# CW340_USBHUB.net
KiCad netlist of a schematic drawn in Altium Designer
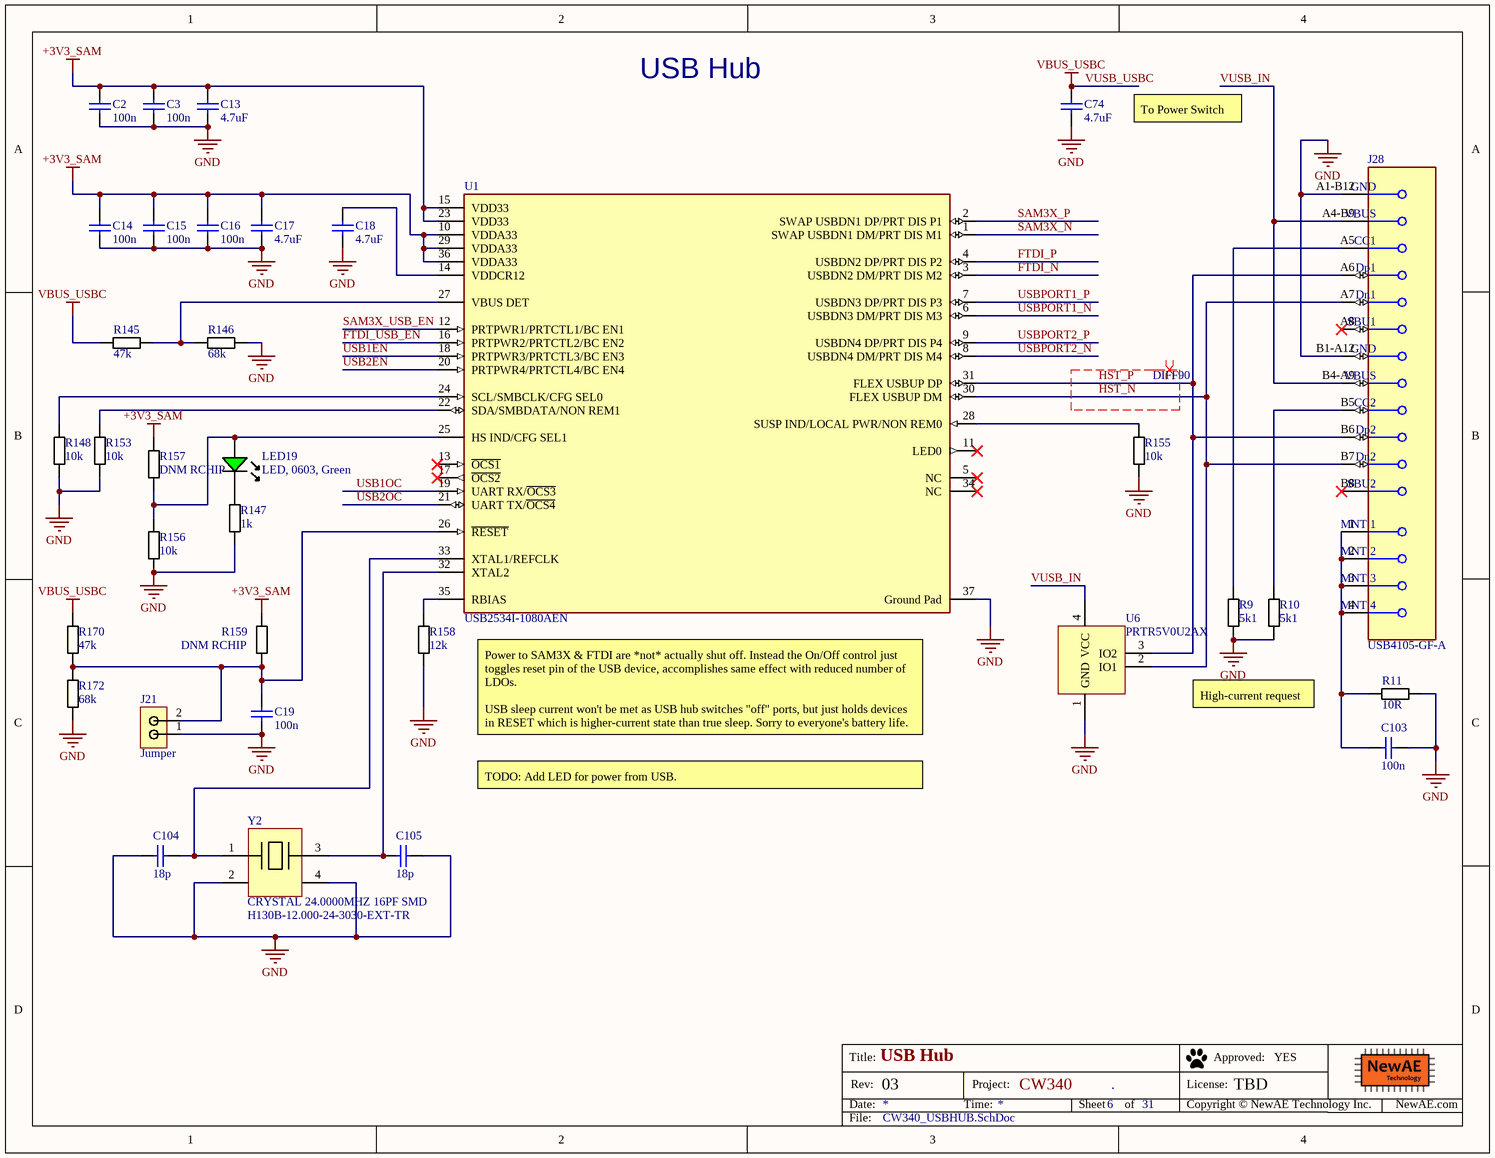
[diagram p0: CW340_USBHUB.SchDoc]

(export (version "E")
  (design (tool "Eeschema 10.0.6"))
  (components
    (comp (ref "C2")
      (value "100n")
      (footprint "CAPC0402_M")
      (description "100n, 0402")
      (fields (field (name "PART NUMBER") "CCHIP-100n-0402"))
      (libsource (lib "NewAE_AltiumLib") (part "CAP"))
    )
    (comp (ref "C3")
      (value "100n")
      (footprint "CAPC0402_M")
      (description "100n, 0402")
      (fields (field (name "PART NUMBER") "CCHIP-100n-0402"))
      (libsource (lib "NewAE_AltiumLib") (part "CAP"))
    )
    (comp (ref "C13")
      (value "4.7uF")
      (footprint "CAPC0805_M")
      (description "4u7, 35V, 0805, Ceramic")
      (fields (field (name "PART NUMBER") "CCHIP-4u7-0805-35V") (field (name "TOLERANCE") "10%"))
      (libsource (lib "NewAE_AltiumLib") (part "CAP"))
    )
    (comp (ref "C14")
      (value "100n")
      (footprint "CAPC0402_M")
      (description "100n, 0402")
      (fields (field (name "PART NUMBER") "CCHIP-100n-0402"))
      (libsource (lib "NewAE_AltiumLib") (part "CAP"))
    )
    (comp (ref "C15")
      (value "100n")
      (footprint "CAPC0402_M")
      (description "100n, 0402")
      (fields (field (name "PART NUMBER") "CCHIP-100n-0402"))
      (libsource (lib "NewAE_AltiumLib") (part "CAP"))
    )
    (comp (ref "C16")
      (value "100n")
      (footprint "CAPC0402_M")
      (description "100n, 0402")
      (fields (field (name "PART NUMBER") "CCHIP-100n-0402"))
      (libsource (lib "NewAE_AltiumLib") (part "CAP"))
    )
    (comp (ref "C17")
      (value "4.7uF")
      (footprint "CAPC0805_M")
      (description "4u7, 35V, 0805, Ceramic")
      (fields (field (name "PART NUMBER") "CCHIP-4u7-0805-35V") (field (name "TOLERANCE") "10%"))
      (libsource (lib "NewAE_AltiumLib") (part "CAP"))
    )
    (comp (ref "C18")
      (value "4.7uF")
      (footprint "CAPC0805_M")
      (description "4u7, 35V, 0805, Ceramic")
      (fields (field (name "PART NUMBER") "CCHIP-4u7-0805-35V") (field (name "TOLERANCE") "10%"))
      (libsource (lib "NewAE_AltiumLib") (part "CAP"))
    )
    (comp (ref "C19")
      (value "100n")
      (footprint "CAPC0402_M")
      (description "100n, 0402")
      (fields (field (name "PART NUMBER") "CCHIP-100n-0402"))
      (libsource (lib "NewAE_AltiumLib") (part "CAP"))
    )
    (comp (ref "C74")
      (value "4.7uF")
      (footprint "CAPC0805_M")
      (description "4u7, 35V, 0805, Ceramic")
      (fields (field (name "PART NUMBER") "CCHIP-4u7-0805-35V") (field (name "TOLERANCE") "10%"))
      (libsource (lib "NewAE_AltiumLib") (part "CAP"))
    )
    (comp (ref "C103")
      (value "100n")
      (footprint "CAPC0603_M")
      (description "100n, 0603")
      (fields (field (name "PART NUMBER") "CCHIP-100n-0603"))
      (libsource (lib "NewAE_AltiumLib") (part "CAP"))
    )
    (comp (ref "C104")
      (value "18p")
      (footprint "CAPC0402_M")
      (description "18p, 0402")
      (fields (field (name "PART NUMBER") "CCHIP-18p-0402"))
      (libsource (lib "NewAE_AltiumLib") (part "CAP"))
    )
    (comp (ref "C105")
      (value "18p")
      (footprint "CAPC0402_M")
      (description "18p, 0402")
      (fields (field (name "PART NUMBER") "CCHIP-18p-0402"))
      (libsource (lib "NewAE_AltiumLib") (part "CAP"))
    )
    (comp (ref "J21")
      (value "Jumper")
      (footprint "2x2.54mm_Header")
      (description "1x2 2.54mm header, male pins")
      (fields (field (name "PART NUMBER") "2_PIN_JUMPER"))
      (libsource (lib "NewAE_AltiumLib") (part "1x2_Pin_Header"))
    )
    (comp (ref "J28")
      (value "USB4105-GF-A")
      (footprint "FP-USB4105-GF-A-MFG")
      (description "CONN RCPT USB2.0 TYPEC 5A")
      (fields
        (field (name "MANUFACTURER") "GCT")
        (field (name "OCTOPART") "https://octopart.com/usb4105-gf-a-gct-106627878")
      )
      (libsource (lib "Altium Content Vault") (part "e7c17a616881a82b79941196b4bec10"))
    )
    (comp (ref "LED19")
      (value "LED, 0603, Green")
      (footprint "LED-0603-GREEN")
      (description "Chip LED, Green")
      (fields (field (name "PART NUMBER") "LEDCHIP_0603_GREEN"))
      (libsource (lib "NewAE_AltiumLib") (part "LED_GREEN"))
    )
    (comp (ref "R9")
      (value "5k1")
      (footprint "RESC1608X55N")
      (description "5k1 res, 0603, 1%, 1/10W")
      (fields (field (name "PART NUMBER") "RCHIP-5K1-0603") (field (name "TOLERANCE") "1%"))
      (libsource (lib "") (part "RES-EU_2"))
    )
    (comp (ref "R10")
      (value "5k1")
      (footprint "RESC1608X55N")
      (description "5k1 res, 0603, 1%, 1/10W")
      (fields (field (name "PART NUMBER") "RCHIP-5K1-0603") (field (name "TOLERANCE") "1%"))
      (libsource (lib "") (part "RES-EU_2"))
    )
    (comp (ref "R11")
      (value "10R")
      (footprint "RESC1608X55N")
      (description "10R res, 0603, 1%, 1/10W")
      (fields (field (name "PART NUMBER") "RCHIP-10R-0603") (field (name "TOLERANCE") "1%"))
      (libsource (lib "") (part "RES-EU_1"))
    )
    (comp (ref "R145")
      (value "47k")
      (footprint "RESC1608X55N")
      (description "47k res, 0603, 1%, 1/10W")
      (fields (field (name "PART NUMBER") "RCHIP-47K-0603") (field (name "TOLERANCE") "1%"))
      (libsource (lib "") (part "RES-EU_1"))
    )
    (comp (ref "R146")
      (value "68k")
      (footprint "RESC1608X55N")
      (description "68k res, 0603, 1%, 1/10W")
      (fields (field (name "PART NUMBER") "RCHIP-68K-0603") (field (name "TOLERANCE") "1%"))
      (libsource (lib "") (part "RES-EU_1"))
    )
    (comp (ref "R147")
      (value "1k")
      (footprint "RESC1608X55N")
      (description "1k res, 0603, 1%, 1/10W")
      (fields (field (name "PART NUMBER") "RCHIP-1K-0603") (field (name "TOLERANCE") "1%"))
      (libsource (lib "") (part "RES-EU_2"))
    )
    (comp (ref "R148")
      (value "10k")
      (footprint "RESC1608X55N")
      (description "10k res, 0603, 1%, 1/10W")
      (fields (field (name "PART NUMBER") "RCHIP-10K-0603") (field (name "TOLERANCE") "1%"))
      (libsource (lib "NewAE_AltiumLib") (part "RES-EU"))
    )
    (comp (ref "R153")
      (value "10k")
      (footprint "RESC1608X55N")
      (description "10k res, 0603, 1%, 1/10W")
      (fields (field (name "PART NUMBER") "RCHIP-10K-0603") (field (name "TOLERANCE") "1%"))
      (libsource (lib "NewAE_AltiumLib") (part "RES-EU"))
    )
    (comp (ref "R155")
      (value "10k")
      (footprint "RESC1608X55N")
      (description "10k res, 0603, 1%, 1/10W")
      (fields (field (name "PART NUMBER") "RCHIP-10K-0603") (field (name "TOLERANCE") "1%"))
      (libsource (lib "NewAE_AltiumLib") (part "RES-EU"))
    )
    (comp (ref "R156")
      (value "10k")
      (footprint "RESC1608X55N")
      (description "10k res, 0603, 1%, 1/10W")
      (fields (field (name "PART NUMBER") "RCHIP-10K-0603") (field (name "TOLERANCE") "1%"))
      (libsource (lib "") (part "RES-EU_2"))
    )
    (comp (ref "R157")
      (value "DNM RCHIP")
      (footprint "RESC1608X55N")
      (description "Do Not Mount Resistor")
      (fields (field (name "PART NUMBER") "RCHIP-DNM-0603"))
      (libsource (lib "") (part "RES-EU_2"))
    )
    (comp (ref "R158")
      (value "12k")
      (footprint "RESC1608X55N")
      (description "12k res, 0603, 1%, 1/10W")
      (fields (field (name "PART NUMBER") "RCHIP-12K-0603") (field (name "TOLERANCE") "1%"))
      (libsource (lib "") (part "RES-EU_2"))
    )
    (comp (ref "R159")
      (value "DNM RCHIP")
      (footprint "RESC1608X55N")
      (description "Do Not Mount Resistor")
      (fields (field (name "PART NUMBER") "RCHIP-DNM-0603"))
      (libsource (lib "") (part "RES-EU_2"))
    )
    (comp (ref "R170")
      (value "47k")
      (footprint "RESC1608X55N")
      (description "47k res, 0603, 1%, 1/10W")
      (fields (field (name "PART NUMBER") "RCHIP-47K-0603") (field (name "TOLERANCE") "1%"))
      (libsource (lib "") (part "RES-EU_2"))
    )
    (comp (ref "R172")
      (value "68k")
      (footprint "RESC1608X55N")
      (description "68k res, 0603, 1%, 1/10W")
      (fields (field (name "PART NUMBER") "RCHIP-68K-0603") (field (name "TOLERANCE") "1%"))
      (libsource (lib "NewAE_AltiumLib") (part "RES-EU"))
    )
    (comp (ref "U1")
      (value "USB2534I-1080AEN")
      (footprint "FP-36SQFN-3706-6x6B-IPC_C")
      (description "IC USB 2.0 HUB CTLR 4PORT 36SQFN")
      (libsource (lib "Altium Content Vault") (part "de4cb607940eb19a3e56e20a470d684"))
    )
    (comp (ref "U6")
      (value "PRTR5V0U2AX")
      (footprint "SOT143B")
      (description "USB 2.0 high-speed ESD")
      (libsource (lib "CW550_MAIN") (part "PRTR5V0U2AX"))
    )
    (comp (ref "Y2")
      (value "CRYSTAL 24.0000MHZ 16PF SMD")
      (footprint "5x3.2MM XTAL")
      (description "24MHz ±30ppm Crystal 16pF 35 Ohms 4-SMD, No Lead")
      (fields
        (field (name "MANUFACTURER") "Raltron Electronics")
        (field (name "MANUFACTURER PART NUMBER") "H130B-12.000-24-3030-EXT-TR")
        (field (name "PART NUMBER") "H130B-24.000-18-3030-EXT-TR")
      )
      (libsource (lib "NewAE_AltiumLib") (part "H130B-12.000-16-2525-EXT-TR"))
    )
  )
  (nets
    (net (code "1") (name "+3V3_SAM") (class "Default")
      (node (ref "C13") (pin "1") (pinfunction "1_1") (pintype "passive"))
      (node (ref "C14") (pin "1") (pinfunction "1_1") (pintype "passive"))
      (node (ref "C15") (pin "1") (pinfunction "1_1") (pintype "passive"))
      (node (ref "C16") (pin "1") (pinfunction "1_1") (pintype "passive"))
      (node (ref "C17") (pin "1") (pinfunction "1_1") (pintype "passive"))
      (node (ref "C2") (pin "1") (pinfunction "1_1") (pintype "passive"))
      (node (ref "C3") (pin "1") (pinfunction "1_1") (pintype "passive"))
      (node (ref "R157") (pin "1") (pinfunction "1_1") (pintype "passive"))
      (node (ref "R159") (pin "1") (pinfunction "1_1") (pintype "passive"))
      (node (ref "U1") (pin "10") (pinfunction "VDDA33_10") (pintype "power_in"))
      (node (ref "U1") (pin "15") (pinfunction "VDD33_15") (pintype "power_in"))
      (node (ref "U1") (pin "23") (pinfunction "VDD33_23") (pintype "power_in"))
      (node (ref "U1") (pin "29") (pinfunction "VDDA33_29") (pintype "power_in"))
      (node (ref "U1") (pin "36") (pinfunction "VDDA33_36") (pintype "power_in"))
    )
    (net (code "2") (name "/FTDI_N") (class "Default")
      (node (ref "U1") (pin "3") (pinfunction "USBDN2_DM/PRT_DIS_M2_3") (pintype "bidirectional"))
    )
    (net (code "3") (name "/FTDI_P") (class "Default")
      (node (ref "U1") (pin "4") (pinfunction "USBDN2_DP/PRT_DIS_P2_4") (pintype "bidirectional"))
    )
    (net (code "4") (name "/FTDI_USB_EN") (class "Default")
      (node (ref "U1") (pin "16") (pinfunction "PRTPWR2/PRTCTL2/BC_EN2_16") (pintype "input"))
    )
    (net (code "5") (name "/HST_N") (class "Default")
      (node (ref "J28") (pin "A7") (pinfunction "Dn1_A7") (pintype "bidirectional"))
      (node (ref "J28") (pin "B7") (pinfunction "Dn2_B7") (pintype "bidirectional"))
      (node (ref "U1") (pin "30") (pinfunction "FLEX_USBUP_DM_30") (pintype "bidirectional"))
      (node (ref "U6") (pin "2") (pinfunction "IO1_2") (pintype "passive"))
    )
    (net (code "6") (name "/HST_P") (class "Default")
      (node (ref "J28") (pin "A6") (pinfunction "Dp1_A6") (pintype "bidirectional"))
      (node (ref "J28") (pin "B6") (pinfunction "Dp2_B6") (pintype "bidirectional"))
      (node (ref "U1") (pin "31") (pinfunction "FLEX_USBUP_DP_31") (pintype "bidirectional"))
      (node (ref "U6") (pin "3") (pinfunction "IO2_3") (pintype "passive"))
    )
    (net (code "7") (name "/SAM3X_N") (class "Default")
      (node (ref "U1") (pin "1") (pinfunction "SWAP_USBDN1_DM/PRT_DIS_M1_1") (pintype "bidirectional"))
    )
    (net (code "8") (name "/SAM3X_P") (class "Default")
      (node (ref "U1") (pin "2") (pinfunction "SWAP_USBDN1_DP/PRT_DIS_P1_2") (pintype "bidirectional"))
    )
    (net (code "9") (name "/SAM3X_USB_EN") (class "Default")
      (node (ref "U1") (pin "12") (pinfunction "PRTPWR1/PRTCTL1/BC_EN1_12") (pintype "input"))
    )
    (net (code "10") (name "/USB1EN") (class "Default")
      (node (ref "U1") (pin "18") (pinfunction "PRTPWR3/PRTCTL3/BC_EN3_18") (pintype "input"))
    )
    (net (code "11") (name "/USB1OC") (class "Default")
      (node (ref "U1") (pin "19") (pinfunction "UART_RX/~{OCS3}_19") (pintype "input"))
    )
    (net (code "12") (name "/USB2EN") (class "Default")
      (node (ref "U1") (pin "20") (pinfunction "PRTPWR4/PRTCTL4/BC_EN4_20") (pintype "input"))
    )
    (net (code "13") (name "/USB2OC") (class "Default")
      (node (ref "U1") (pin "21") (pinfunction "UART_TX/~{OCS4}_21") (pintype "bidirectional"))
    )
    (net (code "14") (name "/USBPORT1_N") (class "Default")
      (node (ref "U1") (pin "6") (pinfunction "USBDN3_DM/PRT_DIS_M3_6") (pintype "bidirectional"))
    )
    (net (code "15") (name "/USBPORT1_P") (class "Default")
      (node (ref "U1") (pin "7") (pinfunction "USBDN3_DP/PRT_DIS_P3_7") (pintype "bidirectional"))
    )
    (net (code "16") (name "/USBPORT2_N") (class "Default")
      (node (ref "U1") (pin "8") (pinfunction "USBDN4_DM/PRT_DIS_M4_8") (pintype "bidirectional"))
    )
    (net (code "17") (name "/USBPORT2_P") (class "Default")
      (node (ref "U1") (pin "9") (pinfunction "USBDN4_DP/PRT_DIS_P4_9") (pintype "bidirectional"))
    )
    (net (code "18") (name "/VUSB_IN") (class "Default")
      (node (ref "J28") (pin "A4-B9") (pinfunction "VBUS_A4-B9") (pintype "power_in"))
      (node (ref "J28") (pin "B4-A9") (pinfunction "VBUS_B4-A9") (pintype "bidirectional"))
      (node (ref "U6") (pin "4") (pinfunction "VCC_4") (pintype "power_in"))
    )
    (net (code "19") (name "GND") (class "Default")
      (node (ref "C103") (pin "2") (pinfunction "2_2") (pintype "passive"))
      (node (ref "C104") (pin "1") (pinfunction "1_1") (pintype "passive"))
      (node (ref "C105") (pin "2") (pinfunction "2_2") (pintype "passive"))
      (node (ref "C13") (pin "2") (pinfunction "2_2") (pintype "passive"))
      (node (ref "C14") (pin "2") (pinfunction "2_2") (pintype "passive"))
      (node (ref "C15") (pin "2") (pinfunction "2_2") (pintype "passive"))
      (node (ref "C16") (pin "2") (pinfunction "2_2") (pintype "passive"))
      (node (ref "C17") (pin "2") (pinfunction "2_2") (pintype "passive"))
      (node (ref "C18") (pin "1") (pinfunction "1_1") (pintype "passive"))
      (node (ref "C19") (pin "2") (pinfunction "2_2") (pintype "passive"))
      (node (ref "C2") (pin "2") (pinfunction "2_2") (pintype "passive"))
      (node (ref "C3") (pin "2") (pinfunction "2_2") (pintype "passive"))
      (node (ref "C74") (pin "2") (pinfunction "2_2") (pintype "passive"))
      (node (ref "J21") (pin "1") (pinfunction "1_1") (pintype "passive"))
      (node (ref "J28") (pin "A1-B12") (pinfunction "GND_A1-B12") (pintype "power_in"))
      (node (ref "J28") (pin "B1-A12") (pinfunction "GND_B1-A12") (pintype "bidirectional"))
      (node (ref "R10") (pin "2") (pinfunction "2_2") (pintype "passive"))
      (node (ref "R11") (pin "2") (pinfunction "2_2") (pintype "passive"))
      (node (ref "R146") (pin "2") (pinfunction "2_2") (pintype "passive"))
      (node (ref "R147") (pin "2") (pinfunction "2_2") (pintype "passive"))
      (node (ref "R148") (pin "1") (pinfunction "1_1") (pintype "passive"))
      (node (ref "R153") (pin "1") (pinfunction "1_1") (pintype "passive"))
      (node (ref "R155") (pin "1") (pinfunction "1_1") (pintype "passive"))
      (node (ref "R156") (pin "2") (pinfunction "2_2") (pintype "passive"))
      (node (ref "R158") (pin "2") (pinfunction "2_2") (pintype "passive"))
      (node (ref "R172") (pin "1") (pinfunction "1_1") (pintype "passive"))
      (node (ref "R9") (pin "2") (pinfunction "2_2") (pintype "passive"))
      (node (ref "U1") (pin "37") (pinfunction "Ground_Pad_37") (pintype "power_in"))
      (node (ref "U6") (pin "1") (pinfunction "GND_1") (pintype "power_in"))
      (node (ref "Y2") (pin "2") (pinfunction "2_2") (pintype "passive"))
      (node (ref "Y2") (pin "4") (pinfunction "4_4") (pintype "passive"))
    )
    (net (code "20") (name "Net-(J28-CC1)") (class "Default")
      (node (ref "J28") (pin "A5") (pinfunction "CC1_A5") (pintype "power_in"))
      (node (ref "R9") (pin "1") (pinfunction "1_1") (pintype "passive"))
    )
    (net (code "21") (name "Net-(J28-CC2)") (class "Default")
      (node (ref "J28") (pin "B5") (pinfunction "CC2_B5") (pintype "bidirectional"))
      (node (ref "R10") (pin "1") (pinfunction "1_1") (pintype "passive"))
    )
    (net (code "22") (name "Net-(J28-MNT_1)") (class "Default")
      (node (ref "C103") (pin "1") (pinfunction "1_1") (pintype "passive"))
      (node (ref "J28") (pin "1") (pinfunction "MNT_1_1") (pintype "power_in"))
      (node (ref "J28") (pin "2") (pinfunction "MNT_2_2") (pintype "power_in"))
      (node (ref "J28") (pin "3") (pinfunction "MNT_3_3") (pintype "power_in"))
      (node (ref "J28") (pin "4") (pinfunction "MNT_4_4") (pintype "power_in"))
      (node (ref "R11") (pin "1") (pinfunction "1_1") (pintype "passive"))
    )
    (net (code "23") (name "Net-(LED19-PadK)") (class "Default")
      (node (ref "LED19") (pin "K") (pinfunction "K_K") (pintype "passive"))
      (node (ref "R147") (pin "1") (pinfunction "1_1") (pintype "passive"))
    )
    (net (code "24") (name "Net-(U1-HS_IND{slash}CFG_SEL1)") (class "Default")
      (node (ref "LED19") (pin "A") (pinfunction "A_A") (pintype "passive"))
      (node (ref "R156") (pin "1") (pinfunction "1_1") (pintype "passive"))
      (node (ref "R157") (pin "2") (pinfunction "2_2") (pintype "passive"))
      (node (ref "U1") (pin "25") (pinfunction "HS_IND/CFG_SEL1_25") (pintype "passive"))
    )
    (net (code "25") (name "Net-(U1-RBIAS)") (class "Default")
      (node (ref "R158") (pin "1") (pinfunction "1_1") (pintype "passive"))
      (node (ref "U1") (pin "35") (pinfunction "RBIAS_35") (pintype "passive"))
    )
    (net (code "26") (name "Net-(U1-SCL{slash}SMBCLK{slash}CFG_SEL0)") (class "Default")
      (node (ref "R148") (pin "2") (pinfunction "2_2") (pintype "passive"))
      (node (ref "U1") (pin "24") (pinfunction "SCL/SMBCLK/CFG_SEL0_24") (pintype "input"))
    )
    (net (code "27") (name "Net-(U1-SDA{slash}SMBDATA{slash}NON_REM1)") (class "Default")
      (node (ref "R153") (pin "2") (pinfunction "2_2") (pintype "passive"))
      (node (ref "U1") (pin "22") (pinfunction "SDA/SMBDATA/NON_REM1_22") (pintype "bidirectional"))
    )
    (net (code "28") (name "Net-(U1-SUSP_IND{slash}LOCAL_PWR{slash}NON_REM0)") (class "Default")
      (node (ref "R155") (pin "2") (pinfunction "2_2") (pintype "passive"))
      (node (ref "U1") (pin "28") (pinfunction "SUSP_IND/LOCAL_PWR/NON_REM0_28") (pintype "input"))
    )
    (net (code "29") (name "Net-(U1-VBUS_DET)") (class "Default")
      (node (ref "R145") (pin "2") (pinfunction "2_2") (pintype "passive"))
      (node (ref "R146") (pin "1") (pinfunction "1_1") (pintype "passive"))
      (node (ref "U1") (pin "27") (pinfunction "VBUS_DET_27") (pintype "power_in"))
    )
    (net (code "30") (name "Net-(U1-VDDCR12)") (class "Default")
      (node (ref "C18") (pin "2") (pinfunction "2_2") (pintype "passive"))
      (node (ref "U1") (pin "14") (pinfunction "VDDCR12_14") (pintype "power_in"))
    )
    (net (code "31") (name "Net-(U1-XTAL1{slash}REFCLK)") (class "Default")
      (node (ref "C104") (pin "2") (pinfunction "2_2") (pintype "passive"))
      (node (ref "U1") (pin "33") (pinfunction "XTAL1/REFCLK_33") (pintype "passive"))
      (node (ref "Y2") (pin "1") (pinfunction "1_1") (pintype "passive"))
    )
    (net (code "32") (name "Net-(U1-XTAL2)") (class "Default")
      (node (ref "C105") (pin "1") (pinfunction "1_1") (pintype "passive"))
      (node (ref "U1") (pin "32") (pinfunction "XTAL2_32") (pintype "passive"))
      (node (ref "Y2") (pin "3") (pinfunction "3_3") (pintype "passive"))
    )
    (net (code "33") (name "Net-(U1-~{RESET})") (class "Default")
      (node (ref "C19") (pin "1") (pinfunction "1_1") (pintype "passive"))
      (node (ref "J21") (pin "2") (pinfunction "2_2") (pintype "passive"))
      (node (ref "R159") (pin "2") (pinfunction "2_2") (pintype "passive"))
      (node (ref "R170") (pin "2") (pinfunction "2_2") (pintype "passive"))
      (node (ref "R172") (pin "2") (pinfunction "2_2") (pintype "passive"))
      (node (ref "U1") (pin "26") (pinfunction "~{RESET}_26") (pintype "input"))
    )
    (net (code "34") (name "VBUS_USBC") (class "Default")
      (node (ref "C74") (pin "1") (pinfunction "1_1") (pintype "passive"))
      (node (ref "R145") (pin "1") (pinfunction "1_1") (pintype "passive"))
      (node (ref "R170") (pin "1") (pinfunction "1_1") (pintype "passive"))
    )
    (net (code "35") (name "unconnected-(J28-SBU1-PadA8)") (class "Default")
      (node (ref "J28") (pin "A8") (pinfunction "SBU1_A8") (pintype "bidirectional+no_connect"))
    )
    (net (code "36") (name "unconnected-(J28-SBU2-PadB8)") (class "Default")
      (node (ref "J28") (pin "B8") (pinfunction "SBU2_B8") (pintype "power_in+no_connect"))
    )
    (net (code "37") (name "unconnected-(U1-LED0-Pad11)") (class "Default")
      (node (ref "U1") (pin "11") (pinfunction "LED0_11") (pintype "output+no_connect"))
    )
    (net (code "38") (name "unconnected-(U1-NC-Pad5)") (class "Default")
      (node (ref "U1") (pin "5") (pinfunction "NC_5") (pintype "passive+no_connect"))
    )
    (net (code "39") (name "unconnected-(U1-NC-Pad34)") (class "Default")
      (node (ref "U1") (pin "34") (pinfunction "NC_34") (pintype "passive+no_connect"))
    )
    (net (code "40") (name "unconnected-(U1-~{OCS1}-Pad13)") (class "Default")
      (node (ref "U1") (pin "13") (pinfunction "~{OCS1}_13") (pintype "input+no_connect"))
    )
    (net (code "41") (name "unconnected-(U1-~{OCS2}-Pad17)") (class "Default")
      (node (ref "U1") (pin "17") (pinfunction "~{OCS2}_17") (pintype "output+no_connect"))
    )
  )
)
